# design.net
KiCad netlist of a schematic drawn in Altium Designer
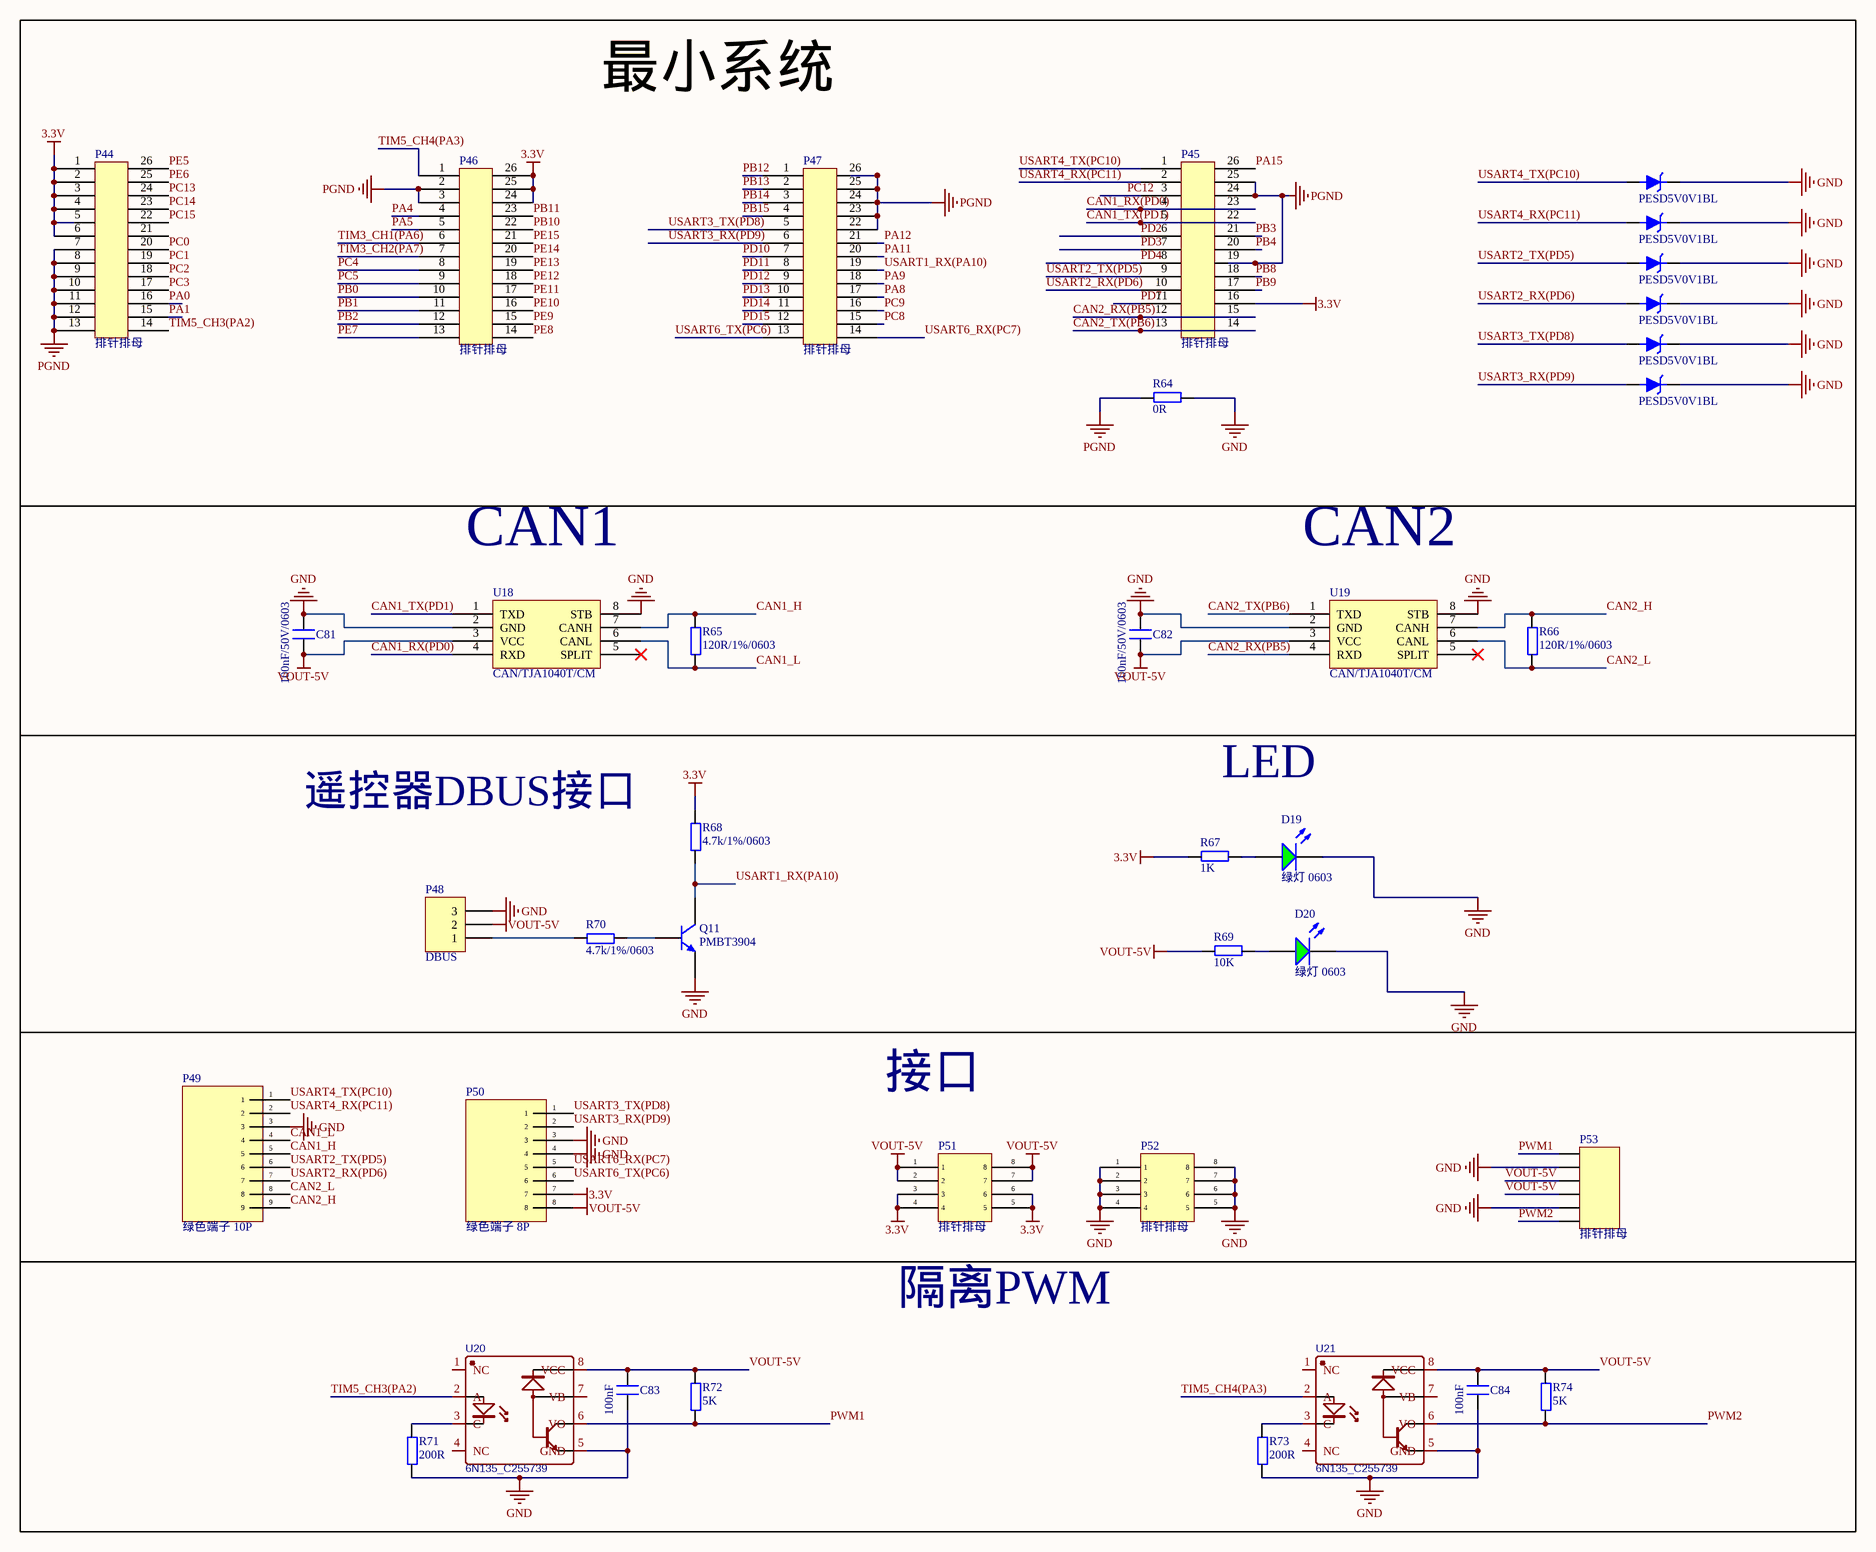
[diagram p0: 底盘扩展板.SchDoc]

(export (version "E")
  (design (tool "Eeschema 10.0.6"))
  (components
    (comp (ref "C81")
      (value "100nF/50V/0603")
      (footprint "0603C  1   2")
      (libsource (lib "Robotmaster") (part "C"))
    )
    (comp (ref "C82")
      (value "100nF/50V/0603")
      (footprint "0603C  1   2")
      (libsource (lib "Robotmaster") (part "C"))
    )
    (comp (ref "C83") (value "100nF") (footprint "C0603") (libsource (lib "Robotmaster") (part "C")))
    (comp (ref "C84") (value "100nF") (footprint "C0603") (libsource (lib "Robotmaster") (part "C")))
    (comp (ref "D19")
      (value "绿灯 0603")
      (footprint "0603_LED_S1")
      (description "发光二极管")
      (libsource (lib "通用板") (part "0603 绿灯"))
    )
    (comp (ref "D20")
      (value "绿灯 0603")
      (footprint "0603_LED_S1")
      (description "发光二极管")
      (libsource (lib "通用板") (part "0603 绿灯"))
    )
    (comp (ref "P44")
      (value "排针排母")
      (footprint "排针 13*2 2.54 立式 -1")
      (libsource (lib "通用主控原理图2") (part "13*2排针"))
    )
    (comp (ref "P45")
      (value "排针排母")
      (footprint "排针 13*2 2.54 立式")
      (libsource (lib "通用主控原理图2") (part "13*2排针"))
    )
    (comp (ref "P46")
      (value "排针排母")
      (footprint "排针 13*2 2.54 立式 -2")
      (libsource (lib "通用主控原理图2") (part "13*2排针"))
    )
    (comp (ref "P47")
      (value "排针排母")
      (footprint "排针 13*2 2.54 立式 -3")
      (libsource (lib "通用主控原理图2") (part "13*2排针"))
    )
    (comp (ref "P48")
      (value "DBUS")
      (footprint "HDR1X3H")
      (description "Header, 3-Pin")
      (fields (field (name "PUBLISHER") "Altium Limited"))
      (libsource (lib "Miscellaneous Connectors") (part "Header 3"))
    )
    (comp (ref "P49") (value "绿色端子 10P") (footprint "绿色端子9p") (libsource (lib "麦轮步兵底盘扩展板") (part "绿色端子 10P")))
    (comp (ref "P50") (value "绿色端子 8P") (footprint "绿色端子8p") (libsource (lib "麦轮步兵底盘扩展板") (part "绿色端子 8P")))
    (comp (ref "P51")
      (value "排针排母")
      (footprint "HDR-TH_16P-P2.54-V-M-R2-C8-S2.54")
      (libsource (lib "麦轮步兵底盘扩展板") (part "排针排母"))
    )
    (comp (ref "P52")
      (value "排针排母")
      (footprint "HDR-TH_16P-P2.54-V-M-R2-C8-S2.54")
      (libsource (lib "麦轮步兵底盘扩展板") (part "排针排母"))
    )
    (comp (ref "P53") (value "排针排母") (libsource (lib "Schlib1") (part "6p排针")))
    (comp (ref "Q11")
      (value "PMBT3904")
      (footprint "SOT-23(SOT-23-3)")
      (description "三极管")
      (libsource (lib "Miscellaneous Devices LC") (part "SOT-23 SS8050 Y1"))
    )
    (comp (ref "R64") (value "0R") (footprint "0603(偏大)") (libsource (lib "Robotmaster") (part "R_1")))
    (comp (ref "R65")
      (value "120R/1%/0603")
      (footprint "0603(偏大)")
      (libsource (lib "Robotmaster") (part "R"))
    )
    (comp (ref "R66")
      (value "120R/1%/0603")
      (footprint "0603(偏大)")
      (libsource (lib "Robotmaster") (part "R"))
    )
    (comp (ref "R67") (value "1K") (footprint "0603(偏大)") (libsource (lib "通用板") (part "R")))
    (comp (ref "R68")
      (value "4.7k/1%/0603")
      (footprint "0603(偏大)")
      (libsource (lib "Robotmaster") (part "R"))
    )
    (comp (ref "R69") (value "10K") (footprint "0603(偏大)") (libsource (lib "通用板") (part "R")))
    (comp (ref "R70")
      (value "4.7k/1%/0603")
      (footprint "0603(偏大)")
      (libsource (lib "Robotmaster") (part "R"))
    )
    (comp (ref "R71") (value "200R") (footprint "0603") (libsource (lib "Robotmaster") (part "R")))
    (comp (ref "R72") (value "5K") (footprint "0603") (libsource (lib "Robotmaster") (part "R")))
    (comp (ref "R73") (value "200R") (footprint "0603") (libsource (lib "Robotmaster") (part "R")))
    (comp (ref "R74") (value "5K") (footprint "0603") (libsource (lib "Robotmaster") (part "R")))
    (comp (ref "T32") (value "PESD5V0V1BL") (footprint "ESD") (libsource (lib "麦轮步兵底盘扩展板") (part "ESD")))
    (comp (ref "T33") (value "PESD5V0V1BL") (footprint "ESD") (libsource (lib "麦轮步兵底盘扩展板") (part "ESD")))
    (comp (ref "T34") (value "PESD5V0V1BL") (footprint "ESD") (libsource (lib "麦轮步兵底盘扩展板") (part "ESD")))
    (comp (ref "T35") (value "PESD5V0V1BL") (footprint "ESD") (libsource (lib "麦轮步兵底盘扩展板") (part "ESD")))
    (comp (ref "T36") (value "PESD5V0V1BL") (footprint "ESD") (libsource (lib "麦轮步兵底盘扩展板") (part "ESD")))
    (comp (ref "T37") (value "PESD5V0V1BL") (footprint "ESD") (libsource (lib "麦轮步兵底盘扩展板") (part "ESD")))
    (comp (ref "U18")
      (value "CAN/TJA1040T/CM")
      (footprint "SOIC-8_150mil")
      (description "CAN")
      (libsource (lib "Miscellaneous Devices LC") (part "CAN/TJA1040T/CM_[C6951]"))
    )
    (comp (ref "U19")
      (value "CAN/TJA1040T/CM")
      (footprint "SOIC-8_150mil")
      (description "CAN")
      (libsource (lib "Miscellaneous Devices LC") (part "CAN/TJA1040T/CM_[C6951]"))
    )
    (comp (ref "U20")
      (value "6N135_C255739")
      (footprint "光耦")
      (fields
        (field (name "BOM_SUPPLIER PART") "C255739")
        (field (name "BOM_MANUFACTURER PART") "6N135")
        (field (name "CONTRIBUTOR") "LCSC")
      )
      (libsource (lib "我的库") (part "6N135_C255739"))
    )
    (comp (ref "U21")
      (value "6N135_C255739")
      (footprint "光耦")
      (fields
        (field (name "BOM_SUPPLIER PART") "C255739")
        (field (name "BOM_MANUFACTURER PART") "6N135")
        (field (name "CONTRIBUTOR") "LCSC")
      )
      (libsource (lib "我的库") (part "6N135_C255739"))
    )
  )
  (nets
    (net (code "1") (name "/CAN1_H") (class "Default")
      (node (ref "P49") (pin "5") (pinfunction "5_5") (pintype "passive"))
      (node (ref "R65") (pin "2") (pintype "passive"))
      (node (ref "U18") (pin "7") (pinfunction "CANH_7") (pintype "passive"))
    )
    (net (code "2") (name "/CAN1_L") (class "Default")
      (node (ref "P49") (pin "4") (pinfunction "4_4") (pintype "passive"))
      (node (ref "R65") (pin "1") (pintype "passive"))
      (node (ref "U18") (pin "6") (pinfunction "CANL_6") (pintype "passive"))
    )
    (net (code "3") (name "/CAN1_RX(PD0)") (class "Default")
      (node (ref "P45") (pin "23") (pinfunction "23_23") (pintype "passive"))
      (node (ref "P45") (pin "4") (pinfunction "4_4") (pintype "passive"))
      (node (ref "U18") (pin "4") (pinfunction "RXD_4") (pintype "passive"))
    )
    (net (code "4") (name "/CAN1_TX(PD1)") (class "Default")
      (node (ref "P45") (pin "22") (pinfunction "22_22") (pintype "passive"))
      (node (ref "P45") (pin "5") (pinfunction "5_5") (pintype "passive"))
      (node (ref "U18") (pin "1") (pinfunction "TXD_1") (pintype "passive"))
    )
    (net (code "5") (name "/CAN2_H") (class "Default")
      (node (ref "P49") (pin "9") (pinfunction "9_9") (pintype "passive"))
      (node (ref "R66") (pin "2") (pintype "passive"))
      (node (ref "U19") (pin "7") (pinfunction "CANH_7") (pintype "passive"))
    )
    (net (code "6") (name "/CAN2_L") (class "Default")
      (node (ref "P49") (pin "8") (pinfunction "8_8") (pintype "passive"))
      (node (ref "R66") (pin "1") (pintype "passive"))
      (node (ref "U19") (pin "6") (pinfunction "CANL_6") (pintype "passive"))
    )
    (net (code "7") (name "/CAN2_RX(PB5)") (class "Default")
      (node (ref "P45") (pin "12") (pinfunction "12_12") (pintype "passive"))
      (node (ref "P45") (pin "15") (pinfunction "15_15") (pintype "passive"))
      (node (ref "U19") (pin "4") (pinfunction "RXD_4") (pintype "passive"))
    )
    (net (code "8") (name "/CAN2_TX(PB6)") (class "Default")
      (node (ref "P45") (pin "13") (pinfunction "13_13") (pintype "passive"))
      (node (ref "P45") (pin "14") (pinfunction "14_14") (pintype "passive"))
      (node (ref "U19") (pin "1") (pinfunction "TXD_1") (pintype "passive"))
    )
    (net (code "9") (name "/PA0") (class "Default")
      (node (ref "P44") (pin "16") (pinfunction "16_16") (pintype "passive"))
    )
    (net (code "10") (name "/PA1") (class "Default")
      (node (ref "P44") (pin "15") (pinfunction "15_15") (pintype "passive"))
    )
    (net (code "11") (name "/PA4") (class "Default")
      (node (ref "P46") (pin "4") (pinfunction "4_4") (pintype "passive"))
    )
    (net (code "12") (name "/PA5") (class "Default")
      (node (ref "P46") (pin "5") (pinfunction "5_5") (pintype "passive"))
    )
    (net (code "13") (name "/PA8") (class "Default")
      (node (ref "P47") (pin "17") (pinfunction "17_17") (pintype "passive"))
    )
    (net (code "14") (name "/PA9") (class "Default")
      (node (ref "P47") (pin "18") (pinfunction "18_18") (pintype "passive"))
    )
    (net (code "15") (name "/PA11") (class "Default")
      (node (ref "P47") (pin "20") (pinfunction "20_20") (pintype "passive"))
    )
    (net (code "16") (name "/PA12") (class "Default")
      (node (ref "P47") (pin "21") (pinfunction "21_21") (pintype "passive"))
    )
    (net (code "17") (name "/PA15") (class "Default")
      (node (ref "P45") (pin "26") (pinfunction "26_26") (pintype "passive"))
    )
    (net (code "18") (name "/PB0") (class "Default")
      (node (ref "P46") (pin "10") (pinfunction "10_10") (pintype "passive"))
    )
    (net (code "19") (name "/PB1") (class "Default")
      (node (ref "P46") (pin "11") (pinfunction "11_11") (pintype "passive"))
    )
    (net (code "20") (name "/PB2") (class "Default")
      (node (ref "P46") (pin "12") (pinfunction "12_12") (pintype "passive"))
    )
    (net (code "21") (name "/PB3") (class "Default")
      (node (ref "P45") (pin "21") (pinfunction "21_21") (pintype "passive"))
    )
    (net (code "22") (name "/PB4") (class "Default")
      (node (ref "P45") (pin "20") (pinfunction "20_20") (pintype "passive"))
    )
    (net (code "23") (name "/PB8") (class "Default")
      (node (ref "P45") (pin "18") (pinfunction "18_18") (pintype "passive"))
    )
    (net (code "24") (name "/PB9") (class "Default")
      (node (ref "P45") (pin "17") (pinfunction "17_17") (pintype "passive"))
    )
    (net (code "25") (name "/PB10") (class "Default")
      (node (ref "P46") (pin "22") (pinfunction "22_22") (pintype "passive"))
    )
    (net (code "26") (name "/PB11") (class "Default")
      (node (ref "P46") (pin "23") (pinfunction "23_23") (pintype "passive"))
    )
    (net (code "27") (name "/PB12") (class "Default")
      (node (ref "P47") (pin "1") (pinfunction "1_1") (pintype "passive"))
    )
    (net (code "28") (name "/PB13") (class "Default")
      (node (ref "P47") (pin "2") (pinfunction "2_2") (pintype "passive"))
    )
    (net (code "29") (name "/PB14") (class "Default")
      (node (ref "P47") (pin "3") (pinfunction "3_3") (pintype "passive"))
    )
    (net (code "30") (name "/PB15") (class "Default")
      (node (ref "P47") (pin "4") (pinfunction "4_4") (pintype "passive"))
    )
    (net (code "31") (name "/PC0") (class "Default")
      (node (ref "P44") (pin "20") (pinfunction "20_20") (pintype "passive"))
    )
    (net (code "32") (name "/PC1") (class "Default")
      (node (ref "P44") (pin "19") (pinfunction "19_19") (pintype "passive"))
    )
    (net (code "33") (name "/PC2") (class "Default")
      (node (ref "P44") (pin "18") (pinfunction "18_18") (pintype "passive"))
    )
    (net (code "34") (name "/PC3") (class "Default")
      (node (ref "P44") (pin "17") (pinfunction "17_17") (pintype "passive"))
    )
    (net (code "35") (name "/PC4") (class "Default")
      (node (ref "P46") (pin "8") (pinfunction "8_8") (pintype "passive"))
    )
    (net (code "36") (name "/PC5") (class "Default")
      (node (ref "P46") (pin "9") (pinfunction "9_9") (pintype "passive"))
    )
    (net (code "37") (name "/PC8") (class "Default")
      (node (ref "P47") (pin "15") (pinfunction "15_15") (pintype "passive"))
    )
    (net (code "38") (name "/PC9") (class "Default")
      (node (ref "P47") (pin "16") (pinfunction "16_16") (pintype "passive"))
    )
    (net (code "39") (name "/PC12") (class "Default")
      (node (ref "P45") (pin "3") (pinfunction "3_3") (pintype "passive"))
    )
    (net (code "40") (name "/PC13") (class "Default")
      (node (ref "P44") (pin "24") (pinfunction "24_24") (pintype "passive"))
    )
    (net (code "41") (name "/PC14") (class "Default")
      (node (ref "P44") (pin "23") (pinfunction "23_23") (pintype "passive"))
    )
    (net (code "42") (name "/PC15") (class "Default")
      (node (ref "P44") (pin "22") (pinfunction "22_22") (pintype "passive"))
    )
    (net (code "43") (name "/PD2") (class "Default")
      (node (ref "P45") (pin "6") (pinfunction "6_6") (pintype "passive"))
    )
    (net (code "44") (name "/PD3") (class "Default")
      (node (ref "P45") (pin "7") (pinfunction "7_7") (pintype "passive"))
    )
    (net (code "45") (name "/PD4") (class "Default")
      (node (ref "P45") (pin "8") (pinfunction "8_8") (pintype "passive"))
    )
    (net (code "46") (name "/PD7") (class "Default")
      (node (ref "P45") (pin "11") (pinfunction "11_11") (pintype "passive"))
    )
    (net (code "47") (name "/PD10") (class "Default")
      (node (ref "P47") (pin "7") (pinfunction "7_7") (pintype "passive"))
    )
    (net (code "48") (name "/PD11") (class "Default")
      (node (ref "P47") (pin "8") (pinfunction "8_8") (pintype "passive"))
    )
    (net (code "49") (name "/PD12") (class "Default")
      (node (ref "P47") (pin "9") (pinfunction "9_9") (pintype "passive"))
    )
    (net (code "50") (name "/PD13") (class "Default")
      (node (ref "P47") (pin "10") (pinfunction "10_10") (pintype "passive"))
    )
    (net (code "51") (name "/PD14") (class "Default")
      (node (ref "P47") (pin "11") (pinfunction "11_11") (pintype "passive"))
    )
    (net (code "52") (name "/PD15") (class "Default")
      (node (ref "P47") (pin "12") (pinfunction "12_12") (pintype "passive"))
    )
    (net (code "53") (name "/PE5") (class "Default")
      (node (ref "P44") (pin "26") (pinfunction "26_26") (pintype "passive"))
    )
    (net (code "54") (name "/PE6") (class "Default")
      (node (ref "P44") (pin "25") (pinfunction "25_25") (pintype "passive"))
    )
    (net (code "55") (name "/PE7") (class "Default")
      (node (ref "P46") (pin "13") (pinfunction "13_13") (pintype "passive"))
    )
    (net (code "56") (name "/PE8") (class "Default")
      (node (ref "P46") (pin "14") (pinfunction "14_14") (pintype "passive"))
    )
    (net (code "57") (name "/PE9") (class "Default")
      (node (ref "P46") (pin "15") (pinfunction "15_15") (pintype "passive"))
    )
    (net (code "58") (name "/PE10") (class "Default")
      (node (ref "P46") (pin "16") (pinfunction "16_16") (pintype "passive"))
    )
    (net (code "59") (name "/PE11") (class "Default")
      (node (ref "P46") (pin "17") (pinfunction "17_17") (pintype "passive"))
    )
    (net (code "60") (name "/PE12") (class "Default")
      (node (ref "P46") (pin "18") (pinfunction "18_18") (pintype "passive"))
    )
    (net (code "61") (name "/PE13") (class "Default")
      (node (ref "P46") (pin "19") (pinfunction "19_19") (pintype "passive"))
    )
    (net (code "62") (name "/PE14") (class "Default")
      (node (ref "P46") (pin "20") (pinfunction "20_20") (pintype "passive"))
    )
    (net (code "63") (name "/PE15") (class "Default")
      (node (ref "P46") (pin "21") (pinfunction "21_21") (pintype "passive"))
    )
    (net (code "64") (name "/PWM1") (class "Default")
      (node (ref "P53") (pin "1") (pinfunction "1_1") (pintype "passive"))
      (node (ref "R72") (pin "1") (pintype "passive"))
      (node (ref "U20") (pin "6") (pinfunction "VO_6") (pintype "passive"))
    )
    (net (code "65") (name "/PWM2") (class "Default")
      (node (ref "P53") (pin "6") (pinfunction "6_6") (pintype "passive"))
      (node (ref "R74") (pin "1") (pintype "passive"))
      (node (ref "U21") (pin "6") (pinfunction "VO_6") (pintype "passive"))
    )
    (net (code "66") (name "/TIM3_CH1(PA6)") (class "Default")
      (node (ref "P46") (pin "6") (pinfunction "6_6") (pintype "passive"))
    )
    (net (code "67") (name "/TIM3_CH2(PA7)") (class "Default")
      (node (ref "P46") (pin "7") (pinfunction "7_7") (pintype "passive"))
    )
    (net (code "68") (name "/TIM5_CH3(PA2)") (class "Default")
      (node (ref "P44") (pin "14") (pinfunction "14_14") (pintype "passive"))
      (node (ref "U20") (pin "2") (pinfunction "A_2") (pintype "passive"))
    )
    (net (code "69") (name "/TIM5_CH4(PA3)") (class "Default")
      (node (ref "P46") (pin "1") (pinfunction "1_1") (pintype "passive"))
      (node (ref "U21") (pin "2") (pinfunction "A_2") (pintype "passive"))
    )
    (net (code "70") (name "/USART1_RX(PA10)") (class "Default")
      (node (ref "P47") (pin "19") (pinfunction "19_19") (pintype "passive"))
      (node (ref "Q11") (pin "3") (pinfunction "C_3") (pintype "passive"))
      (node (ref "R68") (pin "1") (pintype "passive"))
    )
    (net (code "71") (name "/USART2_RX(PD6)") (class "Default")
      (node (ref "P45") (pin "10") (pinfunction "10_10") (pintype "passive"))
      (node (ref "P49") (pin "7") (pinfunction "7_7") (pintype "passive"))
      (node (ref "T35") (pin "1") (pinfunction "A_1") (pintype "passive"))
    )
    (net (code "72") (name "/USART2_TX(PD5)") (class "Default")
      (node (ref "P45") (pin "9") (pinfunction "9_9") (pintype "passive"))
      (node (ref "P49") (pin "6") (pinfunction "6_6") (pintype "passive"))
      (node (ref "T34") (pin "1") (pinfunction "A_1") (pintype "passive"))
    )
    (net (code "73") (name "/USART3_RX(PD9)") (class "Default")
      (node (ref "P47") (pin "6") (pinfunction "6_6") (pintype "passive"))
      (node (ref "P50") (pin "2") (pinfunction "2_2") (pintype "passive"))
      (node (ref "T37") (pin "1") (pinfunction "A_1") (pintype "passive"))
    )
    (net (code "74") (name "/USART3_TX(PD8)") (class "Default")
      (node (ref "P47") (pin "5") (pinfunction "5_5") (pintype "passive"))
      (node (ref "P50") (pin "1") (pinfunction "1_1") (pintype "passive"))
      (node (ref "T36") (pin "1") (pinfunction "A_1") (pintype "passive"))
    )
    (net (code "75") (name "/USART4_RX(PC11)") (class "Default")
      (node (ref "P45") (pin "2") (pinfunction "2_2") (pintype "passive"))
      (node (ref "P49") (pin "2") (pinfunction "2_2") (pintype "passive"))
      (node (ref "T33") (pin "1") (pinfunction "A_1") (pintype "passive"))
    )
    (net (code "76") (name "/USART4_TX(PC10)") (class "Default")
      (node (ref "P45") (pin "1") (pinfunction "1_1") (pintype "passive"))
      (node (ref "P49") (pin "1") (pinfunction "1_1") (pintype "passive"))
      (node (ref "T32") (pin "1") (pinfunction "A_1") (pintype "passive"))
    )
    (net (code "77") (name "/USART6_RX(PC7)") (class "Default")
      (node (ref "P47") (pin "14") (pinfunction "14_14") (pintype "passive"))
      (node (ref "P50") (pin "5") (pinfunction "5_5") (pintype "passive"))
    )
    (net (code "78") (name "/USART6_TX(PC6)") (class "Default")
      (node (ref "P47") (pin "13") (pinfunction "13_13") (pintype "passive"))
      (node (ref "P50") (pin "6") (pinfunction "6_6") (pintype "passive"))
    )
    (net (code "79") (name "3.3V") (class "Default")
      (node (ref "P44") (pin "1") (pinfunction "1_1") (pintype "passive"))
      (node (ref "P44") (pin "2") (pinfunction "2_2") (pintype "passive"))
      (node (ref "P44") (pin "3") (pinfunction "3_3") (pintype "passive"))
      (node (ref "P44") (pin "4") (pinfunction "4_4") (pintype "passive"))
      (node (ref "P44") (pin "5") (pinfunction "5_5") (pintype "passive"))
      (node (ref "P44") (pin "6") (pinfunction "6_6") (pintype "passive"))
      (node (ref "P45") (pin "16") (pinfunction "16_16") (pintype "passive"))
      (node (ref "P46") (pin "24") (pinfunction "24_24") (pintype "passive"))
      (node (ref "P46") (pin "25") (pinfunction "25_25") (pintype "passive"))
      (node (ref "P46") (pin "26") (pinfunction "26_26") (pintype "passive"))
      (node (ref "P50") (pin "7") (pinfunction "7_7") (pintype "passive"))
      (node (ref "P51") (pin "3") (pinfunction "3_3") (pintype "passive"))
      (node (ref "P51") (pin "4") (pinfunction "4_4") (pintype "passive"))
      (node (ref "P51") (pin "5") (pinfunction "5_5") (pintype "passive"))
      (node (ref "P51") (pin "6") (pinfunction "6_6") (pintype "passive"))
      (node (ref "R67") (pin "2") (pintype "passive"))
      (node (ref "R68") (pin "2") (pintype "passive"))
    )
    (net (code "80") (name "GND") (class "Default")
      (node (ref "C81") (pin "2") (pintype "passive"))
      (node (ref "C82") (pin "2") (pintype "passive"))
      (node (ref "C83") (pin "1") (pintype "passive"))
      (node (ref "C84") (pin "1") (pintype "passive"))
      (node (ref "D19") (pin "K") (pinfunction "K_K") (pintype "passive"))
      (node (ref "D20") (pin "K") (pinfunction "K_K") (pintype "passive"))
      (node (ref "P48") (pin "3") (pinfunction "3_3") (pintype "passive"))
      (node (ref "P49") (pin "3") (pinfunction "3_3") (pintype "passive"))
      (node (ref "P50") (pin "3") (pinfunction "3_3") (pintype "passive"))
      (node (ref "P50") (pin "4") (pinfunction "4_4") (pintype "passive"))
      (node (ref "P52") (pin "1") (pinfunction "1_1") (pintype "passive"))
      (node (ref "P52") (pin "2") (pinfunction "2_2") (pintype "passive"))
      (node (ref "P52") (pin "3") (pinfunction "3_3") (pintype "passive"))
      (node (ref "P52") (pin "4") (pinfunction "4_4") (pintype "passive"))
      (node (ref "P52") (pin "5") (pinfunction "5_5") (pintype "passive"))
      (node (ref "P52") (pin "6") (pinfunction "6_6") (pintype "passive"))
      (node (ref "P52") (pin "7") (pinfunction "7_7") (pintype "passive"))
      (node (ref "P52") (pin "8") (pinfunction "8_8") (pintype "passive"))
      (node (ref "P53") (pin "2") (pinfunction "2_2") (pintype "passive"))
      (node (ref "P53") (pin "5") (pinfunction "5_5") (pintype "passive"))
      (node (ref "Q11") (pin "2") (pinfunction "E_2") (pintype "passive"))
      (node (ref "R64") (pin "1") (pintype "passive"))
      (node (ref "R71") (pin "1") (pintype "passive"))
      (node (ref "R73") (pin "1") (pintype "passive"))
      (node (ref "T32") (pin "2") (pinfunction "K_2") (pintype "passive"))
      (node (ref "T33") (pin "2") (pinfunction "K_2") (pintype "passive"))
      (node (ref "T34") (pin "2") (pinfunction "K_2") (pintype "passive"))
      (node (ref "T35") (pin "2") (pinfunction "K_2") (pintype "passive"))
      (node (ref "T36") (pin "2") (pinfunction "K_2") (pintype "passive"))
      (node (ref "T37") (pin "2") (pinfunction "K_2") (pintype "passive"))
      (node (ref "U18") (pin "2") (pinfunction "GND_2") (pintype "passive"))
      (node (ref "U18") (pin "8") (pinfunction "STB_8") (pintype "passive"))
      (node (ref "U19") (pin "2") (pinfunction "GND_2") (pintype "passive"))
      (node (ref "U19") (pin "8") (pinfunction "STB_8") (pintype "passive"))
      (node (ref "U20") (pin "5") (pinfunction "GND_5") (pintype "passive"))
      (node (ref "U21") (pin "5") (pinfunction "GND_5") (pintype "passive"))
    )
    (net (code "81") (name "Net-(D19-PadA)") (class "Default")
      (node (ref "D19") (pin "A") (pinfunction "A_A") (pintype "passive"))
      (node (ref "R67") (pin "1") (pintype "passive"))
    )
    (net (code "82") (name "Net-(D20-PadA)") (class "Default")
      (node (ref "D20") (pin "A") (pinfunction "A_A") (pintype "passive"))
      (node (ref "R69") (pin "1") (pintype "passive"))
    )
    (net (code "83") (name "Net-(P48-Pad1)") (class "Default")
      (node (ref "P48") (pin "1") (pinfunction "1_1") (pintype "passive"))
      (node (ref "R70") (pin "1") (pintype "passive"))
    )
    (net (code "84") (name "Net-(Q11-B)") (class "Default")
      (node (ref "Q11") (pin "1") (pinfunction "B_1") (pintype "passive"))
      (node (ref "R70") (pin "2") (pintype "passive"))
    )
    (net (code "85") (name "Net-(U20-C)") (class "Default")
      (node (ref "R71") (pin "2") (pintype "passive"))
      (node (ref "U20") (pin "3") (pinfunction "C_3") (pintype "passive"))
    )
    (net (code "86") (name "Net-(U21-C)") (class "Default")
      (node (ref "R73") (pin "2") (pintype "passive"))
      (node (ref "U21") (pin "3") (pinfunction "C_3") (pintype "passive"))
    )
    (net (code "87") (name "PGND") (class "Default")
      (node (ref "P44") (pin "10") (pinfunction "10_10") (pintype "passive"))
      (node (ref "P44") (pin "11") (pinfunction "11_11") (pintype "passive"))
      (node (ref "P44") (pin "12") (pinfunction "12_12") (pintype "passive"))
      (node (ref "P44") (pin "13") (pinfunction "13_13") (pintype "passive"))
      (node (ref "P44") (pin "7") (pinfunction "7_7") (pintype "passive"))
      (node (ref "P44") (pin "8") (pinfunction "8_8") (pintype "passive"))
      (node (ref "P44") (pin "9") (pinfunction "9_9") (pintype "passive"))
      (node (ref "P45") (pin "19") (pinfunction "19_19") (pintype "passive"))
      (node (ref "P45") (pin "24") (pinfunction "24_24") (pintype "passive"))
      (node (ref "P45") (pin "25") (pinfunction "25_25") (pintype "passive"))
      (node (ref "P46") (pin "2") (pinfunction "2_2") (pintype "passive"))
      (node (ref "P46") (pin "3") (pinfunction "3_3") (pintype "passive"))
      (node (ref "P47") (pin "22") (pinfunction "22_22") (pintype "passive"))
      (node (ref "P47") (pin "23") (pinfunction "23_23") (pintype "passive"))
      (node (ref "P47") (pin "24") (pinfunction "24_24") (pintype "passive"))
      (node (ref "P47") (pin "25") (pinfunction "25_25") (pintype "passive"))
      (node (ref "P47") (pin "26") (pinfunction "26_26") (pintype "passive"))
      (node (ref "R64") (pin "2") (pintype "passive"))
    )
    (net (code "88") (name "VOUT-5V") (class "Default")
      (node (ref "C81") (pin "1") (pintype "passive"))
      (node (ref "C82") (pin "1") (pintype "passive"))
      (node (ref "C83") (pin "2") (pintype "passive"))
      (node (ref "C84") (pin "2") (pintype "passive"))
      (node (ref "P48") (pin "2") (pinfunction "2_2") (pintype "passive"))
      (node (ref "P50") (pin "8") (pinfunction "8_8") (pintype "passive"))
      (node (ref "P51") (pin "1") (pinfunction "1_1") (pintype "passive"))
      (node (ref "P51") (pin "2") (pinfunction "2_2") (pintype "passive"))
      (node (ref "P51") (pin "7") (pinfunction "7_7") (pintype "passive"))
      (node (ref "P51") (pin "8") (pinfunction "8_8") (pintype "passive"))
      (node (ref "P53") (pin "3") (pinfunction "3_3") (pintype "passive"))
      (node (ref "P53") (pin "4") (pinfunction "4_4") (pintype "passive"))
      (node (ref "R69") (pin "2") (pintype "passive"))
      (node (ref "R72") (pin "2") (pintype "passive"))
      (node (ref "R74") (pin "2") (pintype "passive"))
      (node (ref "U18") (pin "3") (pinfunction "VCC_3") (pintype "passive"))
      (node (ref "U19") (pin "3") (pinfunction "VCC_3") (pintype "passive"))
      (node (ref "U20") (pin "8") (pinfunction "VCC_8") (pintype "passive"))
      (node (ref "U21") (pin "8") (pinfunction "VCC_8") (pintype "passive"))
    )
    (net (code "89") (name "unconnected-(P44-Pad21)") (class "Default")
      (node (ref "P44") (pin "21") (pinfunction "21_21") (pintype "passive"))
    )
    (net (code "90") (name "unconnected-(U18-SPLIT-Pad5)") (class "Default")
      (node (ref "U18") (pin "5") (pinfunction "SPLIT_5") (pintype "passive+no_connect"))
    )
    (net (code "91") (name "unconnected-(U19-SPLIT-Pad5)") (class "Default")
      (node (ref "U19") (pin "5") (pinfunction "SPLIT_5") (pintype "passive+no_connect"))
    )
    (net (code "92") (name "unconnected-(U20-NC-Pad1)") (class "Default")
      (node (ref "U20") (pin "1") (pinfunction "NC_1") (pintype "passive"))
    )
    (net (code "93") (name "unconnected-(U20-NC-Pad4)") (class "Default")
      (node (ref "U20") (pin "4") (pinfunction "NC_4") (pintype "passive"))
    )
    (net (code "94") (name "unconnected-(U20-VB-Pad7)") (class "Default")
      (node (ref "U20") (pin "7") (pinfunction "VB_7") (pintype "passive"))
    )
    (net (code "95") (name "unconnected-(U21-NC-Pad1)") (class "Default")
      (node (ref "U21") (pin "1") (pinfunction "NC_1") (pintype "passive"))
    )
    (net (code "96") (name "unconnected-(U21-NC-Pad4)") (class "Default")
      (node (ref "U21") (pin "4") (pinfunction "NC_4") (pintype "passive"))
    )
    (net (code "97") (name "unconnected-(U21-VB-Pad7)") (class "Default")
      (node (ref "U21") (pin "7") (pinfunction "VB_7") (pintype "passive"))
    )
  )
)
